# expander.net
KiCad netlist of a schematic drawn in EAGLE
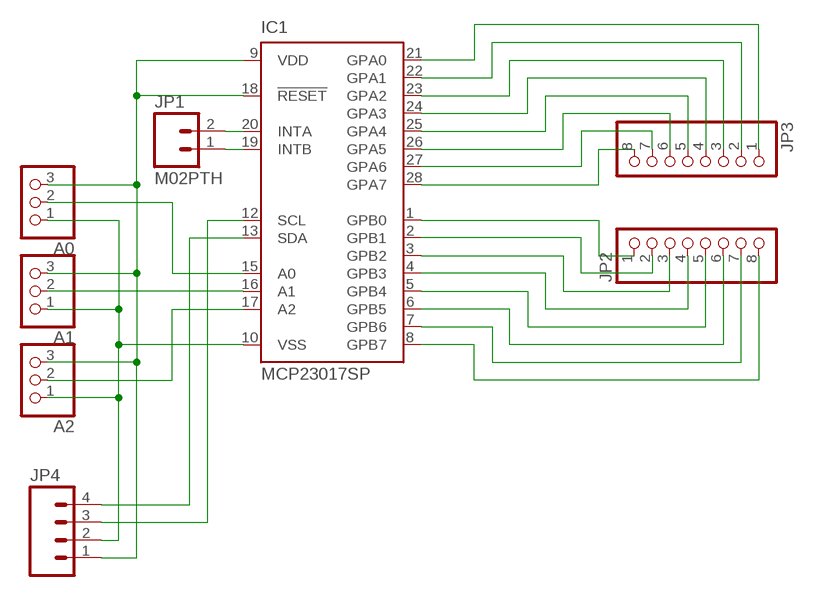
[diagram p0: schematic, sheet 1]

(export (version "E")
  (design (tool "Eeschema 10.0.6"))
  (components
    (comp (ref "A0")
      (value "PINHD-1X3")
      (footprint "eagle-import:1X03")
      (libsource (lib "eagle-import") (part "PINHD-1X3"))
    )
    (comp (ref "A1")
      (value "PINHD-1X3")
      (footprint "eagle-import:1X03")
      (libsource (lib "eagle-import") (part "PINHD-1X3"))
    )
    (comp (ref "A2")
      (value "PINHD-1X3")
      (footprint "eagle-import:1X03")
      (libsource (lib "eagle-import") (part "PINHD-1X3"))
    )
    (comp (ref "IC1")
      (value "MCP23017SP")
      (footprint "eagle-import:DIL28-3")
      (fields (field (name "MF") "MICROCHIP") (field (name "MPN") "MCP23017-E/SP"))
      (libsource (lib "eagle-import") (part "MCP23017SP"))
    )
    (comp (ref "JP1")
      (value "M02PTH")
      (footprint "eagle-import:1X02")
      (libsource (lib "eagle-import") (part "M02PTH"))
    )
    (comp (ref "JP2")
      (value "PINHD-1X8")
      (footprint "eagle-import:1X08")
      (libsource (lib "eagle-import") (part "PINHD-1X8"))
    )
    (comp (ref "JP3")
      (value "PINHD-1X8")
      (footprint "eagle-import:1X08")
      (libsource (lib "eagle-import") (part "PINHD-1X8"))
    )
    (comp (ref "JP4")
      (value "M04POLAR")
      (footprint "eagle-import:MOLEX-1X4")
      (libsource (lib "eagle-import") (part "M04POLAR"))
    )
  )
  (nets
    (net (code "1") (name "Net-(IC1-A0)") (class "Default")
      (node (ref "A0") (pin "2") (pinfunction "2_2") (pintype "passive"))
      (node (ref "IC1") (pin "15") (pinfunction "A0_15") (pintype "input"))
    )
    (net (code "2") (name "Net-(IC1-A1)") (class "Default")
      (node (ref "A1") (pin "2") (pinfunction "2_2") (pintype "passive"))
      (node (ref "IC1") (pin "16") (pinfunction "A1_16") (pintype "input"))
    )
    (net (code "3") (name "Net-(IC1-A2)") (class "Default")
      (node (ref "A2") (pin "2") (pinfunction "2_2") (pintype "passive"))
      (node (ref "IC1") (pin "17") (pinfunction "A2_17") (pintype "input"))
    )
    (net (code "4") (name "Net-(IC1-GPA0)") (class "Default")
      (node (ref "IC1") (pin "21") (pinfunction "GPA0_21") (pintype "bidirectional"))
      (node (ref "JP3") (pin "1") (pinfunction "1_1") (pintype "passive"))
    )
    (net (code "5") (name "Net-(IC1-GPA1)") (class "Default")
      (node (ref "IC1") (pin "22") (pinfunction "GPA1_22") (pintype "bidirectional"))
      (node (ref "JP3") (pin "2") (pinfunction "2_2") (pintype "passive"))
    )
    (net (code "6") (name "Net-(IC1-GPA2)") (class "Default")
      (node (ref "IC1") (pin "23") (pinfunction "GPA2_23") (pintype "bidirectional"))
      (node (ref "JP3") (pin "3") (pinfunction "3_3") (pintype "passive"))
    )
    (net (code "7") (name "Net-(IC1-GPA3)") (class "Default")
      (node (ref "IC1") (pin "24") (pinfunction "GPA3_24") (pintype "bidirectional"))
      (node (ref "JP3") (pin "4") (pinfunction "4_4") (pintype "passive"))
    )
    (net (code "8") (name "Net-(IC1-GPA4)") (class "Default")
      (node (ref "IC1") (pin "25") (pinfunction "GPA4_25") (pintype "bidirectional"))
      (node (ref "JP3") (pin "5") (pinfunction "5_5") (pintype "passive"))
    )
    (net (code "9") (name "Net-(IC1-GPA5)") (class "Default")
      (node (ref "IC1") (pin "26") (pinfunction "GPA5_26") (pintype "bidirectional"))
      (node (ref "JP3") (pin "6") (pinfunction "6_6") (pintype "passive"))
    )
    (net (code "10") (name "Net-(IC1-GPA6)") (class "Default")
      (node (ref "IC1") (pin "27") (pinfunction "GPA6_27") (pintype "bidirectional"))
      (node (ref "JP3") (pin "7") (pinfunction "7_7") (pintype "passive"))
    )
    (net (code "11") (name "Net-(IC1-GPA7)") (class "Default")
      (node (ref "IC1") (pin "28") (pinfunction "GPA7_28") (pintype "bidirectional"))
      (node (ref "JP3") (pin "8") (pinfunction "8_8") (pintype "passive"))
    )
    (net (code "12") (name "Net-(IC1-GPB0)") (class "Default")
      (node (ref "IC1") (pin "1") (pinfunction "GPB0_1") (pintype "bidirectional"))
      (node (ref "JP2") (pin "1") (pinfunction "1_1") (pintype "passive"))
    )
    (net (code "13") (name "Net-(IC1-GPB1)") (class "Default")
      (node (ref "IC1") (pin "2") (pinfunction "GPB1_2") (pintype "bidirectional"))
      (node (ref "JP2") (pin "2") (pinfunction "2_2") (pintype "passive"))
    )
    (net (code "14") (name "Net-(IC1-GPB2)") (class "Default")
      (node (ref "IC1") (pin "3") (pinfunction "GPB2_3") (pintype "bidirectional"))
      (node (ref "JP2") (pin "3") (pinfunction "3_3") (pintype "passive"))
    )
    (net (code "15") (name "Net-(IC1-GPB3)") (class "Default")
      (node (ref "IC1") (pin "4") (pinfunction "GPB3_4") (pintype "bidirectional"))
      (node (ref "JP2") (pin "4") (pinfunction "4_4") (pintype "passive"))
    )
    (net (code "16") (name "Net-(IC1-GPB4)") (class "Default")
      (node (ref "IC1") (pin "5") (pinfunction "GPB4_5") (pintype "bidirectional"))
      (node (ref "JP2") (pin "5") (pinfunction "5_5") (pintype "passive"))
    )
    (net (code "17") (name "Net-(IC1-GPB5)") (class "Default")
      (node (ref "IC1") (pin "6") (pinfunction "GPB5_6") (pintype "bidirectional"))
      (node (ref "JP2") (pin "6") (pinfunction "6_6") (pintype "passive"))
    )
    (net (code "18") (name "Net-(IC1-GPB6)") (class "Default")
      (node (ref "IC1") (pin "7") (pinfunction "GPB6_7") (pintype "bidirectional"))
      (node (ref "JP2") (pin "7") (pinfunction "7_7") (pintype "passive"))
    )
    (net (code "19") (name "Net-(IC1-GPB7)") (class "Default")
      (node (ref "IC1") (pin "8") (pinfunction "GPB7_8") (pintype "bidirectional"))
      (node (ref "JP2") (pin "8") (pinfunction "8_8") (pintype "passive"))
    )
    (net (code "20") (name "Net-(IC1-INTA)") (class "Default")
      (node (ref "IC1") (pin "20") (pinfunction "INTA_20") (pintype "output"))
      (node (ref "JP1") (pin "2") (pinfunction "2_2") (pintype "passive"))
    )
    (net (code "21") (name "Net-(IC1-INTB)") (class "Default")
      (node (ref "IC1") (pin "19") (pinfunction "INTB_19") (pintype "output"))
      (node (ref "JP1") (pin "1") (pinfunction "1_1") (pintype "passive"))
    )
    (net (code "22") (name "Net-(IC1-SCL)") (class "Default")
      (node (ref "IC1") (pin "12") (pinfunction "SCL_12") (pintype "input"))
      (node (ref "JP4") (pin "3") (pinfunction "3_3") (pintype "passive"))
    )
    (net (code "23") (name "Net-(IC1-SDA)") (class "Default")
      (node (ref "IC1") (pin "13") (pinfunction "SDA_13") (pintype "bidirectional"))
      (node (ref "JP4") (pin "4") (pinfunction "4_4") (pintype "passive"))
    )
    (net (code "24") (name "Net-(IC1-VDD)") (class "Default")
      (node (ref "A0") (pin "3") (pinfunction "3_3") (pintype "passive"))
      (node (ref "A1") (pin "3") (pinfunction "3_3") (pintype "passive"))
      (node (ref "A2") (pin "3") (pinfunction "3_3") (pintype "passive"))
      (node (ref "IC1") (pin "18") (pinfunction "~{RESET}_18") (pintype "input"))
      (node (ref "IC1") (pin "9") (pinfunction "VDD_9") (pintype "power_in"))
      (node (ref "JP4") (pin "1") (pinfunction "1_1") (pintype "passive"))
    )
    (net (code "25") (name "Net-(IC1-VSS)") (class "Default")
      (node (ref "A0") (pin "1") (pinfunction "1_1") (pintype "passive"))
      (node (ref "A1") (pin "1") (pinfunction "1_1") (pintype "passive"))
      (node (ref "A2") (pin "1") (pinfunction "1_1") (pintype "passive"))
      (node (ref "IC1") (pin "10") (pinfunction "VSS_10") (pintype "power_in"))
      (node (ref "JP4") (pin "2") (pinfunction "2_2") (pintype "passive"))
    )
  )
)
